# untitled.net
KiCad netlist of a schematic drawn in EAGLE
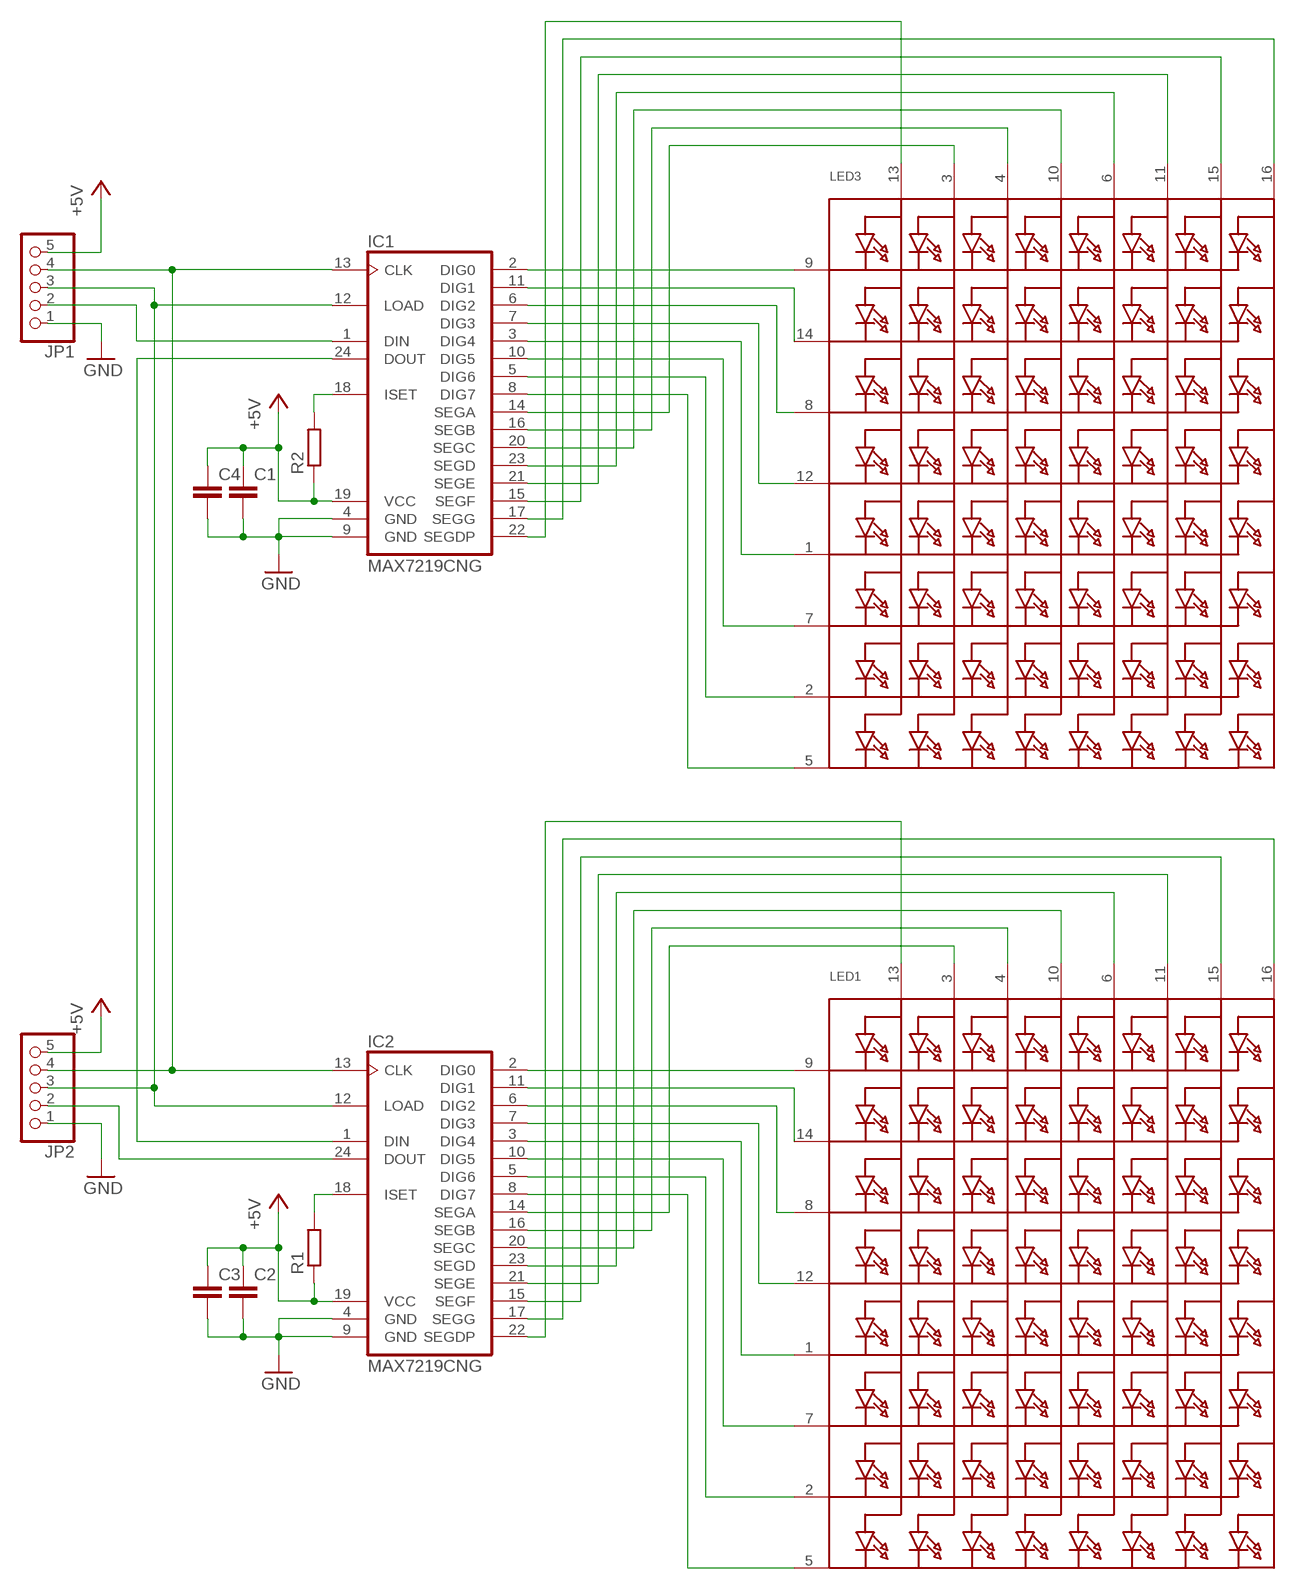
[diagram p0: schematic, sheet 1]

(export (version "E")
  (design (tool "Eeschema 10.0.6"))
  (components
    (comp (ref "C1")
      (value "C-EUC0805K")
      (footprint "eagle-import:C0805K")
      (libsource (lib "eagle-import") (part "C-EUC0805K"))
    )
    (comp (ref "C2")
      (value "C-EUC0805K")
      (footprint "eagle-import:C0805K")
      (libsource (lib "eagle-import") (part "C-EUC0805K"))
    )
    (comp (ref "C3")
      (value "C-EUC0805K")
      (footprint "eagle-import:C0805K")
      (libsource (lib "eagle-import") (part "C-EUC0805K"))
    )
    (comp (ref "C4")
      (value "C-EUC0805K")
      (footprint "eagle-import:C0805K")
      (libsource (lib "eagle-import") (part "C-EUC0805K"))
    )
    (comp (ref "IC1")
      (value "MAX7219CNG")
      (footprint "eagle-import:DIL24-3")
      (fields (field (name "MF") "MAXIM"))
      (libsource (lib "eagle-import") (part "MAX7219CNG"))
    )
    (comp (ref "IC2")
      (value "MAX7219CNG")
      (footprint "eagle-import:DIL24-3")
      (fields (field (name "MF") "MAXIM"))
      (libsource (lib "eagle-import") (part "MAX7219CNG"))
    )
    (comp (ref "JP1")
      (value "PINHD-1X5/90")
      (footprint "eagle-import:1X05_90")
      (libsource (lib "eagle-import") (part "PINHD-1X5/90"))
    )
    (comp (ref "JP2")
      (value "PINHD-1X5/90")
      (footprint "eagle-import:1X05_90")
      (libsource (lib "eagle-import") (part "PINHD-1X5/90"))
    )
    (comp (ref "LED1")
      (value "SEGMENT_8X8_ROWCATHODEM12A881UR")
      (footprint "eagle-import:SEGMENT_BL-M12A881UR")
      (libsource (lib "eagle-import") (part "SEGMENT_8X8_ROWCATHODEM12A881UR"))
    )
    (comp (ref "LED3")
      (value "SEGMENT_8X8_ROWCATHODEM12A881UR")
      (footprint "eagle-import:SEGMENT_BL-M12A881UR")
      (libsource (lib "eagle-import") (part "SEGMENT_8X8_ROWCATHODEM12A881UR"))
    )
    (comp (ref "R1")
      (value "R-EU_M0805")
      (footprint "eagle-import:M0805")
      (libsource (lib "eagle-import") (part "R-EU_M0805"))
    )
    (comp (ref "R2")
      (value "R-EU_M0805")
      (footprint "eagle-import:M0805")
      (libsource (lib "eagle-import") (part "R-EU_M0805"))
    )
  )
  (nets
    (net (code "1") (name "+5V") (class "Default")
      (node (ref "C1") (pin "1") (pinfunction "1_1") (pintype "passive"))
      (node (ref "C2") (pin "1") (pinfunction "1_1") (pintype "passive"))
      (node (ref "C3") (pin "1") (pinfunction "1_1") (pintype "passive"))
      (node (ref "C4") (pin "1") (pinfunction "1_1") (pintype "passive"))
      (node (ref "IC1") (pin "19") (pinfunction "VCC_19") (pintype "power_in"))
      (node (ref "IC2") (pin "19") (pinfunction "VCC_19") (pintype "power_in"))
      (node (ref "JP1") (pin "5") (pinfunction "5_5") (pintype "passive"))
      (node (ref "JP2") (pin "5") (pinfunction "5_5") (pintype "passive"))
      (node (ref "R1") (pin "1") (pinfunction "1_1") (pintype "passive"))
      (node (ref "R2") (pin "1") (pinfunction "1_1") (pintype "passive"))
    )
    (net (code "2") (name "GND") (class "Default")
      (node (ref "C1") (pin "2") (pinfunction "2_2") (pintype "passive"))
      (node (ref "C2") (pin "2") (pinfunction "2_2") (pintype "passive"))
      (node (ref "C3") (pin "2") (pinfunction "2_2") (pintype "passive"))
      (node (ref "C4") (pin "2") (pinfunction "2_2") (pintype "passive"))
      (node (ref "IC1") (pin "4") (pinfunction "GND_4") (pintype "power_in"))
      (node (ref "IC1") (pin "9") (pinfunction "GND_9") (pintype "power_in"))
      (node (ref "IC2") (pin "4") (pinfunction "GND_4") (pintype "power_in"))
      (node (ref "IC2") (pin "9") (pinfunction "GND_9") (pintype "power_in"))
      (node (ref "JP1") (pin "1") (pinfunction "1_1") (pintype "passive"))
      (node (ref "JP2") (pin "1") (pinfunction "1_1") (pintype "passive"))
    )
    (net (code "3") (name "Net-(IC1-CLK)") (class "Default")
      (node (ref "IC1") (pin "13") (pinfunction "CLK_13") (pintype "input"))
      (node (ref "IC2") (pin "13") (pinfunction "CLK_13") (pintype "input"))
      (node (ref "JP1") (pin "4") (pinfunction "4_4") (pintype "passive"))
      (node (ref "JP2") (pin "4") (pinfunction "4_4") (pintype "passive"))
    )
    (net (code "4") (name "Net-(IC1-DIG0)") (class "Default")
      (node (ref "IC1") (pin "2") (pinfunction "DIG0_2") (pintype "output"))
      (node (ref "LED3") (pin "9") (pinfunction "K1_9") (pintype "bidirectional"))
    )
    (net (code "5") (name "Net-(IC1-DIG1)") (class "Default")
      (node (ref "IC1") (pin "11") (pinfunction "DIG1_11") (pintype "output"))
      (node (ref "LED3") (pin "14") (pinfunction "K2_14") (pintype "bidirectional"))
    )
    (net (code "6") (name "Net-(IC1-DIG2)") (class "Default")
      (node (ref "IC1") (pin "6") (pinfunction "DIG2_6") (pintype "output"))
      (node (ref "LED3") (pin "8") (pinfunction "K3_8") (pintype "bidirectional"))
    )
    (net (code "7") (name "Net-(IC1-DIG3)") (class "Default")
      (node (ref "IC1") (pin "7") (pinfunction "DIG3_7") (pintype "output"))
      (node (ref "LED3") (pin "12") (pinfunction "K4_12") (pintype "bidirectional"))
    )
    (net (code "8") (name "Net-(IC1-DIG4)") (class "Default")
      (node (ref "IC1") (pin "3") (pinfunction "DIG4_3") (pintype "output"))
      (node (ref "LED3") (pin "1") (pinfunction "K5_1") (pintype "bidirectional"))
    )
    (net (code "9") (name "Net-(IC1-DIG5)") (class "Default")
      (node (ref "IC1") (pin "10") (pinfunction "DIG5_10") (pintype "output"))
      (node (ref "LED3") (pin "7") (pinfunction "K6_7") (pintype "bidirectional"))
    )
    (net (code "10") (name "Net-(IC1-DIG6)") (class "Default")
      (node (ref "IC1") (pin "5") (pinfunction "DIG6_5") (pintype "output"))
      (node (ref "LED3") (pin "2") (pinfunction "K7_2") (pintype "bidirectional"))
    )
    (net (code "11") (name "Net-(IC1-DIG7)") (class "Default")
      (node (ref "IC1") (pin "8") (pinfunction "DIG7_8") (pintype "output"))
      (node (ref "LED3") (pin "5") (pinfunction "K8_5") (pintype "bidirectional"))
    )
    (net (code "12") (name "Net-(IC1-DIN)") (class "Default")
      (node (ref "IC1") (pin "1") (pinfunction "DIN_1") (pintype "input"))
      (node (ref "JP1") (pin "2") (pinfunction "2_2") (pintype "passive"))
    )
    (net (code "13") (name "Net-(IC1-DOUT)") (class "Default")
      (node (ref "IC1") (pin "24") (pinfunction "DOUT_24") (pintype "output"))
      (node (ref "IC2") (pin "1") (pinfunction "DIN_1") (pintype "input"))
    )
    (net (code "14") (name "Net-(IC1-ISET)") (class "Default")
      (node (ref "IC1") (pin "18") (pinfunction "ISET_18") (pintype "input"))
      (node (ref "R2") (pin "2") (pinfunction "2_2") (pintype "passive"))
    )
    (net (code "15") (name "Net-(IC1-LOAD)") (class "Default")
      (node (ref "IC1") (pin "12") (pinfunction "LOAD_12") (pintype "input"))
      (node (ref "IC2") (pin "12") (pinfunction "LOAD_12") (pintype "input"))
      (node (ref "JP1") (pin "3") (pinfunction "3_3") (pintype "passive"))
      (node (ref "JP2") (pin "3") (pinfunction "3_3") (pintype "passive"))
    )
    (net (code "16") (name "Net-(IC1-SEGA)") (class "Default")
      (node (ref "IC1") (pin "14") (pinfunction "SEGA_14") (pintype "output"))
      (node (ref "LED3") (pin "3") (pinfunction "A2_3") (pintype "bidirectional"))
    )
    (net (code "17") (name "Net-(IC1-SEGB)") (class "Default")
      (node (ref "IC1") (pin "16") (pinfunction "SEGB_16") (pintype "output"))
      (node (ref "LED3") (pin "4") (pinfunction "A3_4") (pintype "bidirectional"))
    )
    (net (code "18") (name "Net-(IC1-SEGC)") (class "Default")
      (node (ref "IC1") (pin "20") (pinfunction "SEGC_20") (pintype "output"))
      (node (ref "LED3") (pin "10") (pinfunction "A4_10") (pintype "bidirectional"))
    )
    (net (code "19") (name "Net-(IC1-SEGD)") (class "Default")
      (node (ref "IC1") (pin "23") (pinfunction "SEGD_23") (pintype "output"))
      (node (ref "LED3") (pin "6") (pinfunction "A5_6") (pintype "bidirectional"))
    )
    (net (code "20") (name "Net-(IC1-SEGDP)") (class "Default")
      (node (ref "IC1") (pin "22") (pinfunction "SEGDP_22") (pintype "output"))
      (node (ref "LED3") (pin "13") (pinfunction "A1_13") (pintype "bidirectional"))
    )
    (net (code "21") (name "Net-(IC1-SEGE)") (class "Default")
      (node (ref "IC1") (pin "21") (pinfunction "SEGE_21") (pintype "output"))
      (node (ref "LED3") (pin "11") (pinfunction "A6_11") (pintype "bidirectional"))
    )
    (net (code "22") (name "Net-(IC1-SEGF)") (class "Default")
      (node (ref "IC1") (pin "15") (pinfunction "SEGF_15") (pintype "output"))
      (node (ref "LED3") (pin "15") (pinfunction "A7_15") (pintype "bidirectional"))
    )
    (net (code "23") (name "Net-(IC1-SEGG)") (class "Default")
      (node (ref "IC1") (pin "17") (pinfunction "SEGG_17") (pintype "output"))
      (node (ref "LED3") (pin "16") (pinfunction "A8_16") (pintype "bidirectional"))
    )
    (net (code "24") (name "Net-(IC2-DIG0)") (class "Default")
      (node (ref "IC2") (pin "2") (pinfunction "DIG0_2") (pintype "output"))
      (node (ref "LED1") (pin "9") (pinfunction "K1_9") (pintype "bidirectional"))
    )
    (net (code "25") (name "Net-(IC2-DIG1)") (class "Default")
      (node (ref "IC2") (pin "11") (pinfunction "DIG1_11") (pintype "output"))
      (node (ref "LED1") (pin "14") (pinfunction "K2_14") (pintype "bidirectional"))
    )
    (net (code "26") (name "Net-(IC2-DIG2)") (class "Default")
      (node (ref "IC2") (pin "6") (pinfunction "DIG2_6") (pintype "output"))
      (node (ref "LED1") (pin "8") (pinfunction "K3_8") (pintype "bidirectional"))
    )
    (net (code "27") (name "Net-(IC2-DIG3)") (class "Default")
      (node (ref "IC2") (pin "7") (pinfunction "DIG3_7") (pintype "output"))
      (node (ref "LED1") (pin "12") (pinfunction "K4_12") (pintype "bidirectional"))
    )
    (net (code "28") (name "Net-(IC2-DIG4)") (class "Default")
      (node (ref "IC2") (pin "3") (pinfunction "DIG4_3") (pintype "output"))
      (node (ref "LED1") (pin "1") (pinfunction "K5_1") (pintype "bidirectional"))
    )
    (net (code "29") (name "Net-(IC2-DIG5)") (class "Default")
      (node (ref "IC2") (pin "10") (pinfunction "DIG5_10") (pintype "output"))
      (node (ref "LED1") (pin "7") (pinfunction "K6_7") (pintype "bidirectional"))
    )
    (net (code "30") (name "Net-(IC2-DIG6)") (class "Default")
      (node (ref "IC2") (pin "5") (pinfunction "DIG6_5") (pintype "output"))
      (node (ref "LED1") (pin "2") (pinfunction "K7_2") (pintype "bidirectional"))
    )
    (net (code "31") (name "Net-(IC2-DIG7)") (class "Default")
      (node (ref "IC2") (pin "8") (pinfunction "DIG7_8") (pintype "output"))
      (node (ref "LED1") (pin "5") (pinfunction "K8_5") (pintype "bidirectional"))
    )
    (net (code "32") (name "Net-(IC2-DOUT)") (class "Default")
      (node (ref "IC2") (pin "24") (pinfunction "DOUT_24") (pintype "output"))
      (node (ref "JP2") (pin "2") (pinfunction "2_2") (pintype "passive"))
    )
    (net (code "33") (name "Net-(IC2-ISET)") (class "Default")
      (node (ref "IC2") (pin "18") (pinfunction "ISET_18") (pintype "input"))
      (node (ref "R1") (pin "2") (pinfunction "2_2") (pintype "passive"))
    )
    (net (code "34") (name "Net-(IC2-SEGA)") (class "Default")
      (node (ref "IC2") (pin "14") (pinfunction "SEGA_14") (pintype "output"))
      (node (ref "LED1") (pin "3") (pinfunction "A2_3") (pintype "bidirectional"))
    )
    (net (code "35") (name "Net-(IC2-SEGB)") (class "Default")
      (node (ref "IC2") (pin "16") (pinfunction "SEGB_16") (pintype "output"))
      (node (ref "LED1") (pin "4") (pinfunction "A3_4") (pintype "bidirectional"))
    )
    (net (code "36") (name "Net-(IC2-SEGC)") (class "Default")
      (node (ref "IC2") (pin "20") (pinfunction "SEGC_20") (pintype "output"))
      (node (ref "LED1") (pin "10") (pinfunction "A4_10") (pintype "bidirectional"))
    )
    (net (code "37") (name "Net-(IC2-SEGD)") (class "Default")
      (node (ref "IC2") (pin "23") (pinfunction "SEGD_23") (pintype "output"))
      (node (ref "LED1") (pin "6") (pinfunction "A5_6") (pintype "bidirectional"))
    )
    (net (code "38") (name "Net-(IC2-SEGDP)") (class "Default")
      (node (ref "IC2") (pin "22") (pinfunction "SEGDP_22") (pintype "output"))
      (node (ref "LED1") (pin "13") (pinfunction "A1_13") (pintype "bidirectional"))
    )
    (net (code "39") (name "Net-(IC2-SEGE)") (class "Default")
      (node (ref "IC2") (pin "21") (pinfunction "SEGE_21") (pintype "output"))
      (node (ref "LED1") (pin "11") (pinfunction "A6_11") (pintype "bidirectional"))
    )
    (net (code "40") (name "Net-(IC2-SEGF)") (class "Default")
      (node (ref "IC2") (pin "15") (pinfunction "SEGF_15") (pintype "output"))
      (node (ref "LED1") (pin "15") (pinfunction "A7_15") (pintype "bidirectional"))
    )
    (net (code "41") (name "Net-(IC2-SEGG)") (class "Default")
      (node (ref "IC2") (pin "17") (pinfunction "SEGG_17") (pintype "output"))
      (node (ref "LED1") (pin "16") (pinfunction "A8_16") (pintype "bidirectional"))
    )
  )
)
